# H-Bridge_Motor_Ctrl.net
KiCad netlist of a schematic drawn in EAGLE
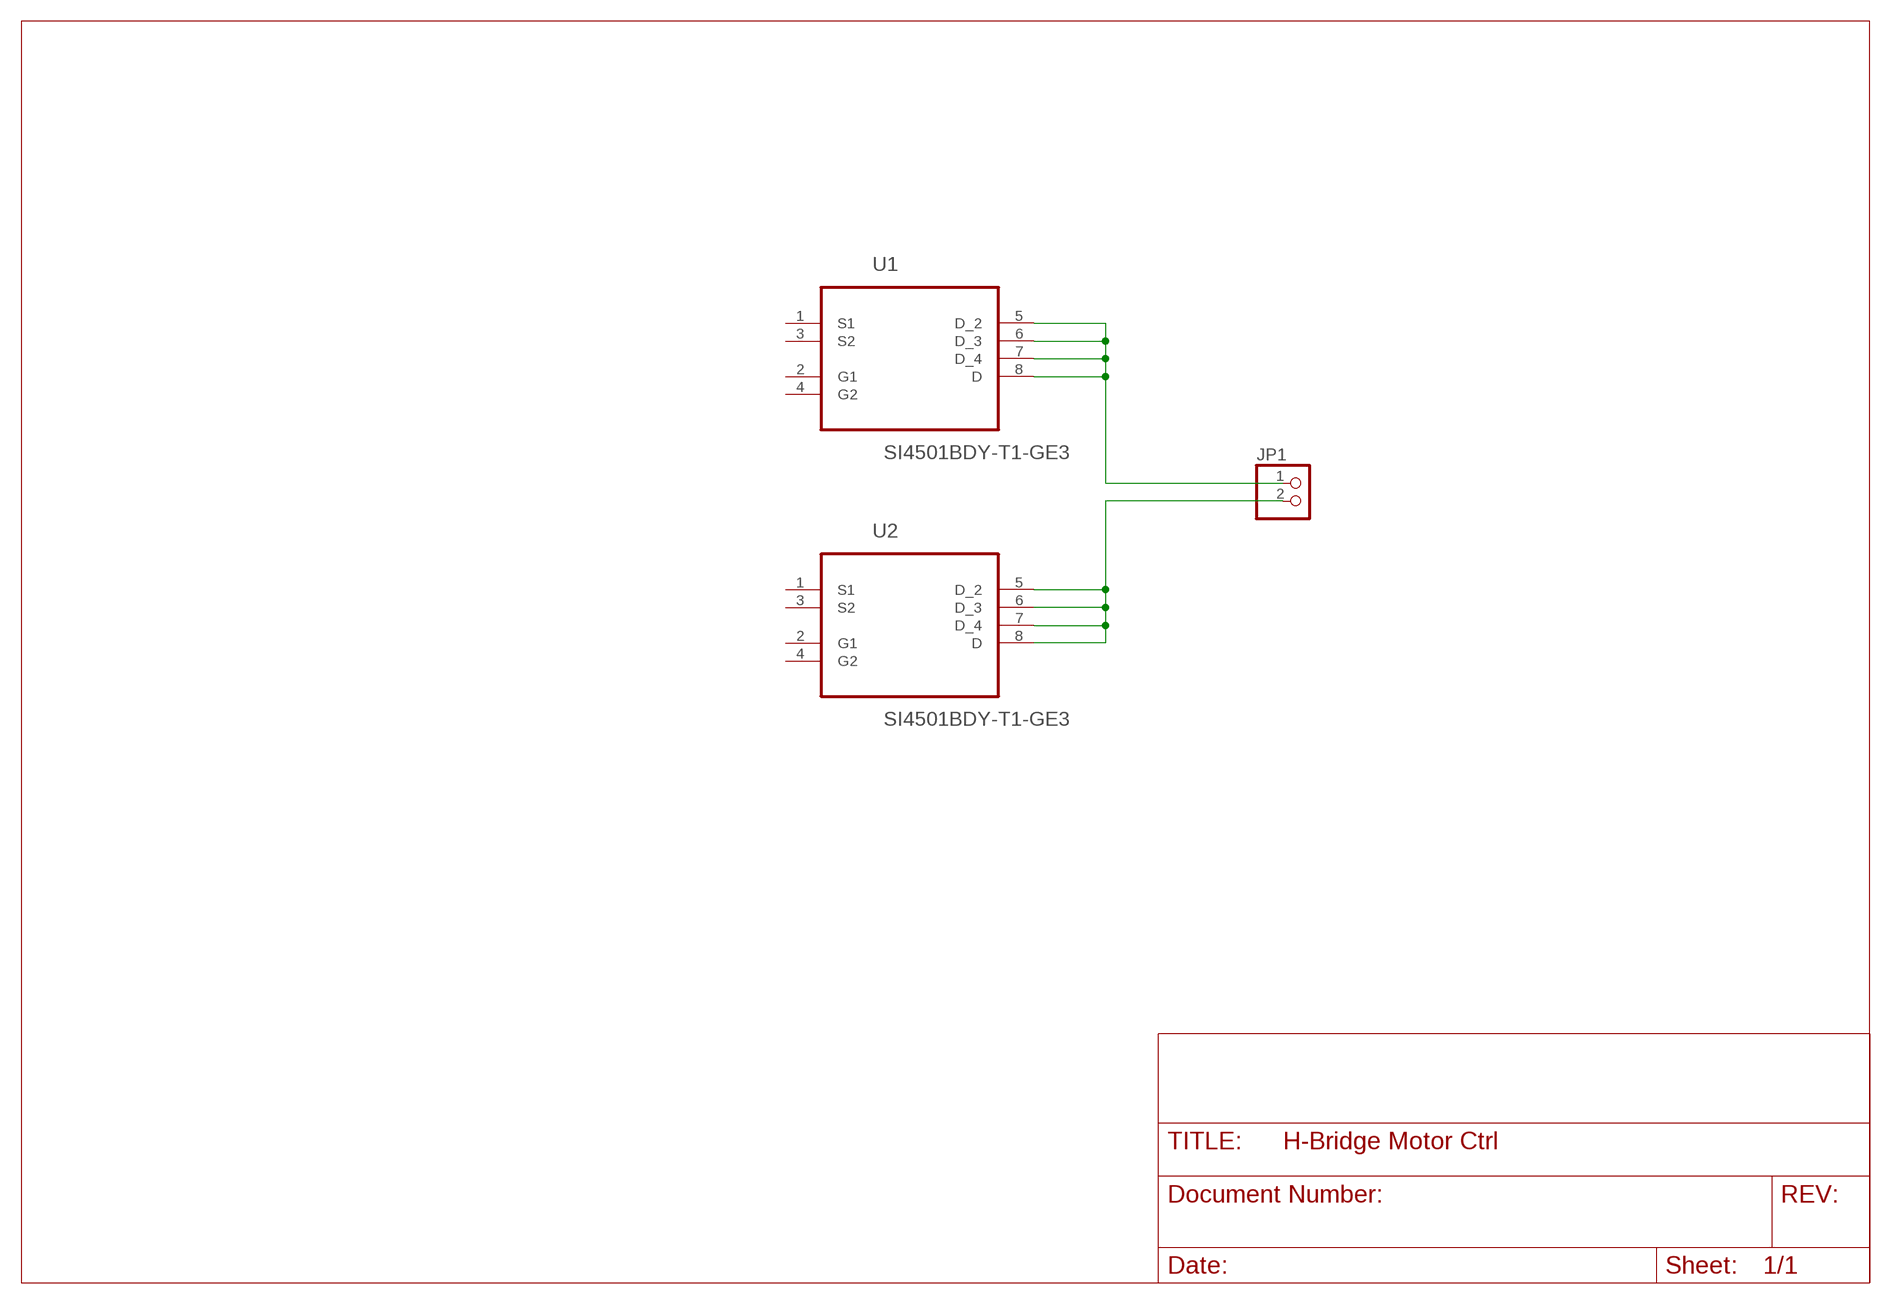
[diagram p0: schematic, sheet 1]

(export (version "E")
  (design (tool "Eeschema 10.0.6"))
  (components
    (comp (ref "JP1")
      (value "PINHD-1X2")
      (footprint "eagle-import:1X02")
      (libsource (lib "eagle-import") (part "PINHD-1X2"))
    )
    (comp (ref "U1")
      (value "SI4501BDY-T1-GE3")
      (footprint "eagle-import:SOIC127P600X175-8N")
      (libsource (lib "eagle-import") (part "SI4501BDY-T1-GE3"))
    )
    (comp (ref "U2")
      (value "SI4501BDY-T1-GE3")
      (footprint "eagle-import:SOIC127P600X175-8N")
      (libsource (lib "eagle-import") (part "SI4501BDY-T1-GE3"))
    )
  )
  (nets
    (net (code "1") (name "Net-(U1-D)") (class "Default")
      (node (ref "JP1") (pin "1") (pinfunction "1_1") (pintype "passive"))
      (node (ref "U1") (pin "5") (pinfunction "D_2_5") (pintype "passive"))
      (node (ref "U1") (pin "6") (pinfunction "D_3_6") (pintype "passive"))
      (node (ref "U1") (pin "7") (pinfunction "D_4_7") (pintype "passive"))
      (node (ref "U1") (pin "8") (pinfunction "D_8") (pintype "passive"))
    )
    (net (code "2") (name "Net-(U2-D)") (class "Default")
      (node (ref "JP1") (pin "2") (pinfunction "2_2") (pintype "passive"))
      (node (ref "U2") (pin "5") (pinfunction "D_2_5") (pintype "passive"))
      (node (ref "U2") (pin "6") (pinfunction "D_3_6") (pintype "passive"))
      (node (ref "U2") (pin "7") (pinfunction "D_4_7") (pintype "passive"))
      (node (ref "U2") (pin "8") (pinfunction "D_8") (pintype "passive"))
    )
    (net (code "3") (name "unconnected-(U1-G1-Pad2)") (class "Default")
      (node (ref "U1") (pin "2") (pinfunction "G1_2") (pintype "passive"))
    )
    (net (code "4") (name "unconnected-(U1-G2-Pad4)") (class "Default")
      (node (ref "U1") (pin "4") (pinfunction "G2_4") (pintype "passive"))
    )
    (net (code "5") (name "unconnected-(U1-S1-Pad1)") (class "Default")
      (node (ref "U1") (pin "1") (pinfunction "S1_1") (pintype "passive"))
    )
    (net (code "6") (name "unconnected-(U1-S2-Pad3)") (class "Default")
      (node (ref "U1") (pin "3") (pinfunction "S2_3") (pintype "passive"))
    )
    (net (code "7") (name "unconnected-(U2-G1-Pad2)") (class "Default")
      (node (ref "U2") (pin "2") (pinfunction "G1_2") (pintype "passive"))
    )
    (net (code "8") (name "unconnected-(U2-G2-Pad4)") (class "Default")
      (node (ref "U2") (pin "4") (pinfunction "G2_4") (pintype "passive"))
    )
    (net (code "9") (name "unconnected-(U2-S1-Pad1)") (class "Default")
      (node (ref "U2") (pin "1") (pinfunction "S1_1") (pintype "passive"))
    )
    (net (code "10") (name "unconnected-(U2-S2-Pad3)") (class "Default")
      (node (ref "U2") (pin "3") (pinfunction "S2_3") (pintype "passive"))
    )
  )
)
